# Connector.net
KiCad netlist of a schematic drawn in Altium Designer
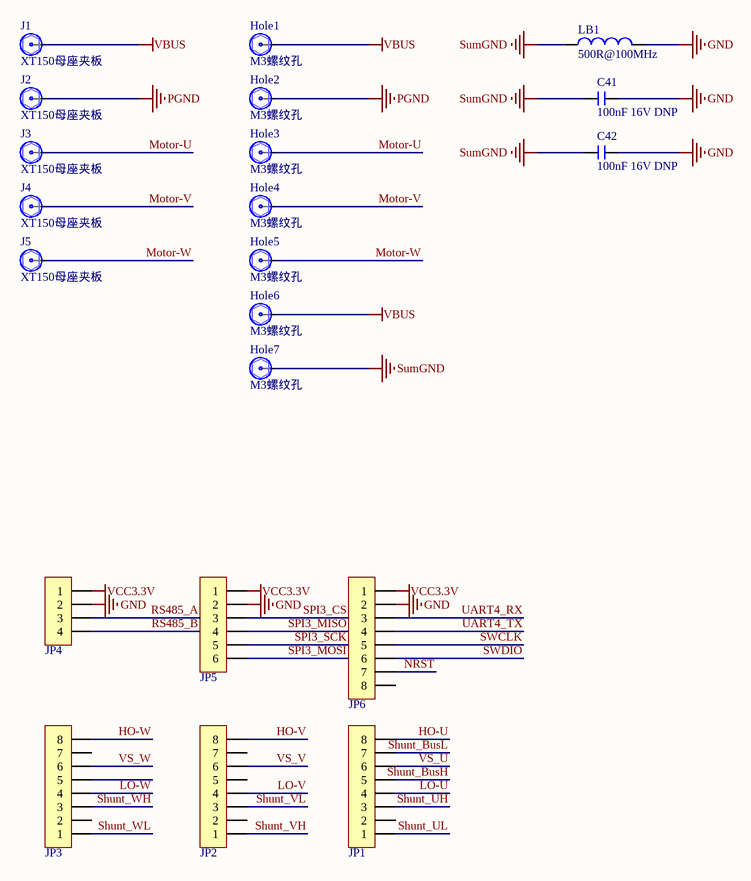
[diagram p0: Connector.SchDoc]

(export (version "E")
  (design (tool "Eeschema 10.0.6"))
  (components
    (comp (ref "C41")
      (value "100nF 16V DNP")
      (footprint "C0603_L")
      (description "独石电容")
      (fields (field (name "版权归属") "源创客"))
      (libsource (lib "Capacitor") (part "C-MLCC"))
    )
    (comp (ref "C42")
      (value "100nF 16V DNP")
      (footprint "C0603_L")
      (description "独石电容")
      (fields (field (name "版权归属") "源创客"))
      (libsource (lib "Capacitor") (part "C-MLCC"))
    )
    (comp (ref "Hole1") (value "M3螺纹孔") (footprint "M3_3*7载流孔_铜柱") (libsource (lib "Hole") (part "M3螺纹孔")))
    (comp (ref "Hole2") (value "M3螺纹孔") (footprint "M3_3*7载流孔_铜柱") (libsource (lib "Hole") (part "M3螺纹孔")))
    (comp (ref "Hole3") (value "M3螺纹孔") (footprint "M3_3*7载流孔_螺丝") (libsource (lib "Hole") (part "M3螺纹孔")))
    (comp (ref "Hole4") (value "M3螺纹孔") (footprint "M3_3*7载流孔_螺丝") (libsource (lib "Hole") (part "M3螺纹孔")))
    (comp (ref "Hole5") (value "M3螺纹孔") (footprint "M3_3*7载流孔_螺丝") (libsource (lib "Hole") (part "M3螺纹孔")))
    (comp (ref "Hole6") (value "M3螺纹孔") (footprint "M3_3*7载流孔_铜柱") (libsource (lib "Hole") (part "M3螺纹孔")))
    (comp (ref "Hole7") (value "M3螺纹孔") (footprint "M3_3*7载流孔_铜柱") (libsource (lib "Hole") (part "M3螺纹孔")))
    (comp (ref "J1")
      (value "XT150母座夹板")
      (footprint "XT150_母座夹板 - VBUS")
      (libsource (lib "Connector-PWR") (part "XT150母座夹板"))
    )
    (comp (ref "J2")
      (value "XT150母座夹板")
      (footprint "XT150_母座夹板 - PGND")
      (libsource (lib "Connector-PWR") (part "XT150母座夹板"))
    )
    (comp (ref "J3")
      (value "XT150母座夹板")
      (footprint "XT150_母座夹板 - duplicate")
      (libsource (lib "Connector-PWR") (part "XT150母座夹板"))
    )
    (comp (ref "J4")
      (value "XT150母座夹板")
      (footprint "XT150_母座夹板")
      (libsource (lib "Connector-PWR") (part "XT150母座夹板"))
    )
    (comp (ref "J5")
      (value "XT150母座夹板")
      (footprint "XT150_母座夹板")
      (libsource (lib "Connector-PWR") (part "XT150母座夹板"))
    )
    (comp (ref "JP1")
      (value "HDR-1X8")
      (footprint "贴片排母2.54mm_交错_8P")
      (description "8P接插件")
      (fields (field (name "版权归属") "源创客"))
      (libsource (lib "") (part "Header 8_1"))
    )
    (comp (ref "JP2")
      (value "HDR-1X8")
      (footprint "贴片排母2.54mm_交错_8P")
      (description "8P接插件")
      (fields (field (name "版权归属") "源创客"))
      (libsource (lib "") (part "Header 8_1"))
    )
    (comp (ref "JP3")
      (value "HDR-1X8")
      (footprint "贴片排母2.54mm_交错_8P")
      (description "8P接插件")
      (fields (field (name "版权归属") "源创客"))
      (libsource (lib "") (part "Header 8_1"))
    )
    (comp (ref "JP4")
      (value "HDR-1X4")
      (footprint "MX 1.25-WS-4P")
      (description "4P接插件")
      (fields (field (name "版权归属") "源创客"))
      (libsource (lib "Connector-PinHeader") (part "Header 4"))
    )
    (comp (ref "JP5")
      (value "HDR-1X6")
      (footprint "MX 1.25-WS-6P")
      (description "6P接插件")
      (fields (field (name "版权归属") "源创客"))
      (libsource (lib "Connector-PinHeader") (part "Header 6"))
    )
    (comp (ref "JP6")
      (value "HDR-1X8")
      (footprint "MX 1.25-WS-8P")
      (description "8P接插件")
      (fields (field (name "版权归属") "源创客"))
      (libsource (lib "Connector-PinHeader") (part "Header 8"))
    )
    (comp (ref "LB1")
      (value "500R@100MHz")
      (footprint "FB 0805_L")
      (description "磁珠")
      (fields (field (name "版权归属") "源创客"))
      (libsource (lib "Inductor") (part "LB"))
    )
  )
  (nets
    (net (code "1") (name "/HO-U") (class "Default")
      (node (ref "JP1") (pin "8") (pinfunction "8_8") (pintype "passive"))
    )
    (net (code "2") (name "/HO-V") (class "Default")
      (node (ref "JP2") (pin "8") (pinfunction "8_8") (pintype "passive"))
    )
    (net (code "3") (name "/HO-W") (class "Default")
      (node (ref "JP3") (pin "8") (pinfunction "8_8") (pintype "passive"))
    )
    (net (code "4") (name "/LO-U") (class "Default")
      (node (ref "JP1") (pin "4") (pinfunction "4_4") (pintype "passive"))
    )
    (net (code "5") (name "/LO-V") (class "Default")
      (node (ref "JP2") (pin "4") (pinfunction "4_4") (pintype "passive"))
    )
    (net (code "6") (name "/LO-W") (class "Default")
      (node (ref "JP3") (pin "4") (pinfunction "4_4") (pintype "passive"))
    )
    (net (code "7") (name "/Motor-U") (class "Default")
      (node (ref "Hole3") (pin "1") (pinfunction "1_1") (pintype "passive"))
      (node (ref "J3") (pin "1") (pinfunction "1_1") (pintype "passive"))
    )
    (net (code "8") (name "/Motor-V") (class "Default")
      (node (ref "Hole4") (pin "1") (pinfunction "1_1") (pintype "passive"))
      (node (ref "J4") (pin "1") (pinfunction "1_1") (pintype "passive"))
    )
    (net (code "9") (name "/Motor-W") (class "Default")
      (node (ref "Hole5") (pin "1") (pinfunction "1_1") (pintype "passive"))
      (node (ref "J5") (pin "1") (pinfunction "1_1") (pintype "passive"))
    )
    (net (code "10") (name "/NRST") (class "Default")
      (node (ref "JP6") (pin "7") (pinfunction "7_7") (pintype "passive"))
    )
    (net (code "11") (name "/RS485_A") (class "Default")
      (node (ref "JP4") (pin "3") (pinfunction "3_3") (pintype "passive"))
    )
    (net (code "12") (name "/RS485_B") (class "Default")
      (node (ref "JP4") (pin "4") (pinfunction "4_4") (pintype "passive"))
    )
    (net (code "13") (name "/SPI3_CS") (class "Default")
      (node (ref "JP5") (pin "3") (pinfunction "3_3") (pintype "passive"))
    )
    (net (code "14") (name "/SPI3_MISO") (class "Default")
      (node (ref "JP5") (pin "4") (pinfunction "4_4") (pintype "passive"))
    )
    (net (code "15") (name "/SPI3_MOSI") (class "Default")
      (node (ref "JP5") (pin "6") (pinfunction "6_6") (pintype "passive"))
    )
    (net (code "16") (name "/SPI3_SCK") (class "Default")
      (node (ref "JP5") (pin "5") (pinfunction "5_5") (pintype "passive"))
    )
    (net (code "17") (name "/SWCLK") (class "Default")
      (node (ref "JP6") (pin "5") (pinfunction "5_5") (pintype "passive"))
    )
    (net (code "18") (name "/SWDIO") (class "Default")
      (node (ref "JP6") (pin "6") (pinfunction "6_6") (pintype "passive"))
    )
    (net (code "19") (name "/Shunt_BusH") (class "Default")
      (node (ref "JP1") (pin "5") (pinfunction "5_5") (pintype "passive"))
    )
    (net (code "20") (name "/Shunt_BusL") (class "Default")
      (node (ref "JP1") (pin "7") (pinfunction "7_7") (pintype "passive"))
    )
    (net (code "21") (name "/Shunt_UH") (class "Default")
      (node (ref "JP1") (pin "3") (pinfunction "3_3") (pintype "passive"))
    )
    (net (code "22") (name "/Shunt_UL") (class "Default")
      (node (ref "JP1") (pin "1") (pinfunction "1_1") (pintype "passive"))
    )
    (net (code "23") (name "/Shunt_VH") (class "Default")
      (node (ref "JP2") (pin "1") (pinfunction "1_1") (pintype "passive"))
    )
    (net (code "24") (name "/Shunt_VL") (class "Default")
      (node (ref "JP2") (pin "3") (pinfunction "3_3") (pintype "passive"))
    )
    (net (code "25") (name "/Shunt_WH") (class "Default")
      (node (ref "JP3") (pin "3") (pinfunction "3_3") (pintype "passive"))
    )
    (net (code "26") (name "/Shunt_WL") (class "Default")
      (node (ref "JP3") (pin "1") (pinfunction "1_1") (pintype "passive"))
    )
    (net (code "27") (name "/UART4_RX") (class "Default")
      (node (ref "JP6") (pin "3") (pinfunction "3_3") (pintype "passive"))
    )
    (net (code "28") (name "/UART4_TX") (class "Default")
      (node (ref "JP6") (pin "4") (pinfunction "4_4") (pintype "passive"))
    )
    (net (code "29") (name "/VS_U") (class "Default")
      (node (ref "JP1") (pin "6") (pinfunction "6_6") (pintype "passive"))
    )
    (net (code "30") (name "/VS_V") (class "Default")
      (node (ref "JP2") (pin "6") (pinfunction "6_6") (pintype "passive"))
    )
    (net (code "31") (name "/VS_W") (class "Default")
      (node (ref "JP3") (pin "6") (pinfunction "6_6") (pintype "passive"))
    )
    (net (code "32") (name "GND") (class "Default")
      (node (ref "C41") (pin "1") (pinfunction "1_1") (pintype "passive"))
      (node (ref "C42") (pin "1") (pinfunction "1_1") (pintype "passive"))
      (node (ref "JP4") (pin "2") (pinfunction "2_2") (pintype "passive"))
      (node (ref "JP5") (pin "2") (pinfunction "2_2") (pintype "passive"))
      (node (ref "JP6") (pin "2") (pinfunction "2_2") (pintype "passive"))
      (node (ref "LB1") (pin "2") (pinfunction "2_2") (pintype "passive"))
    )
    (net (code "33") (name "PGND") (class "Default")
      (node (ref "Hole2") (pin "1") (pinfunction "1_1") (pintype "passive"))
      (node (ref "J2") (pin "1") (pinfunction "1_1") (pintype "passive"))
    )
    (net (code "34") (name "SumGND") (class "Default")
      (node (ref "C41") (pin "2") (pinfunction "2_2") (pintype "passive"))
      (node (ref "C42") (pin "2") (pinfunction "2_2") (pintype "passive"))
      (node (ref "Hole7") (pin "1") (pinfunction "1_1") (pintype "passive"))
      (node (ref "LB1") (pin "1") (pinfunction "1_1") (pintype "passive"))
    )
    (net (code "35") (name "VBUS") (class "Default")
      (node (ref "Hole1") (pin "1") (pinfunction "1_1") (pintype "passive"))
      (node (ref "Hole6") (pin "1") (pinfunction "1_1") (pintype "passive"))
      (node (ref "J1") (pin "1") (pinfunction "1_1") (pintype "passive"))
    )
    (net (code "36") (name "VCC3.3V") (class "Default")
      (node (ref "JP4") (pin "1") (pinfunction "1_1") (pintype "passive"))
      (node (ref "JP5") (pin "1") (pinfunction "1_1") (pintype "passive"))
      (node (ref "JP6") (pin "1") (pinfunction "1_1") (pintype "passive"))
    )
    (net (code "37") (name "unconnected-(JP1-Pad2)") (class "Default")
      (node (ref "JP1") (pin "2") (pinfunction "2_2") (pintype "passive"))
    )
    (net (code "38") (name "unconnected-(JP2-Pad2)") (class "Default")
      (node (ref "JP2") (pin "2") (pinfunction "2_2") (pintype "passive"))
    )
    (net (code "39") (name "unconnected-(JP2-Pad5)") (class "Default")
      (node (ref "JP2") (pin "5") (pinfunction "5_5") (pintype "passive"))
    )
    (net (code "40") (name "unconnected-(JP2-Pad7)") (class "Default")
      (node (ref "JP2") (pin "7") (pinfunction "7_7") (pintype "passive"))
    )
    (net (code "41") (name "unconnected-(JP3-Pad2)") (class "Default")
      (node (ref "JP3") (pin "2") (pinfunction "2_2") (pintype "passive"))
    )
    (net (code "42") (name "unconnected-(JP3-Pad5)") (class "Default")
      (node (ref "JP3") (pin "5") (pinfunction "5_5") (pintype "passive"))
    )
    (net (code "43") (name "unconnected-(JP3-Pad7)") (class "Default")
      (node (ref "JP3") (pin "7") (pinfunction "7_7") (pintype "passive"))
    )
    (net (code "44") (name "unconnected-(JP6-Pad8)") (class "Default")
      (node (ref "JP6") (pin "8") (pinfunction "8_8") (pintype "passive"))
    )
  )
)
